# lm3410-boost-flashlight-driver-20mm-mk-1.net
KiCad netlist of a schematic drawn in EAGLE
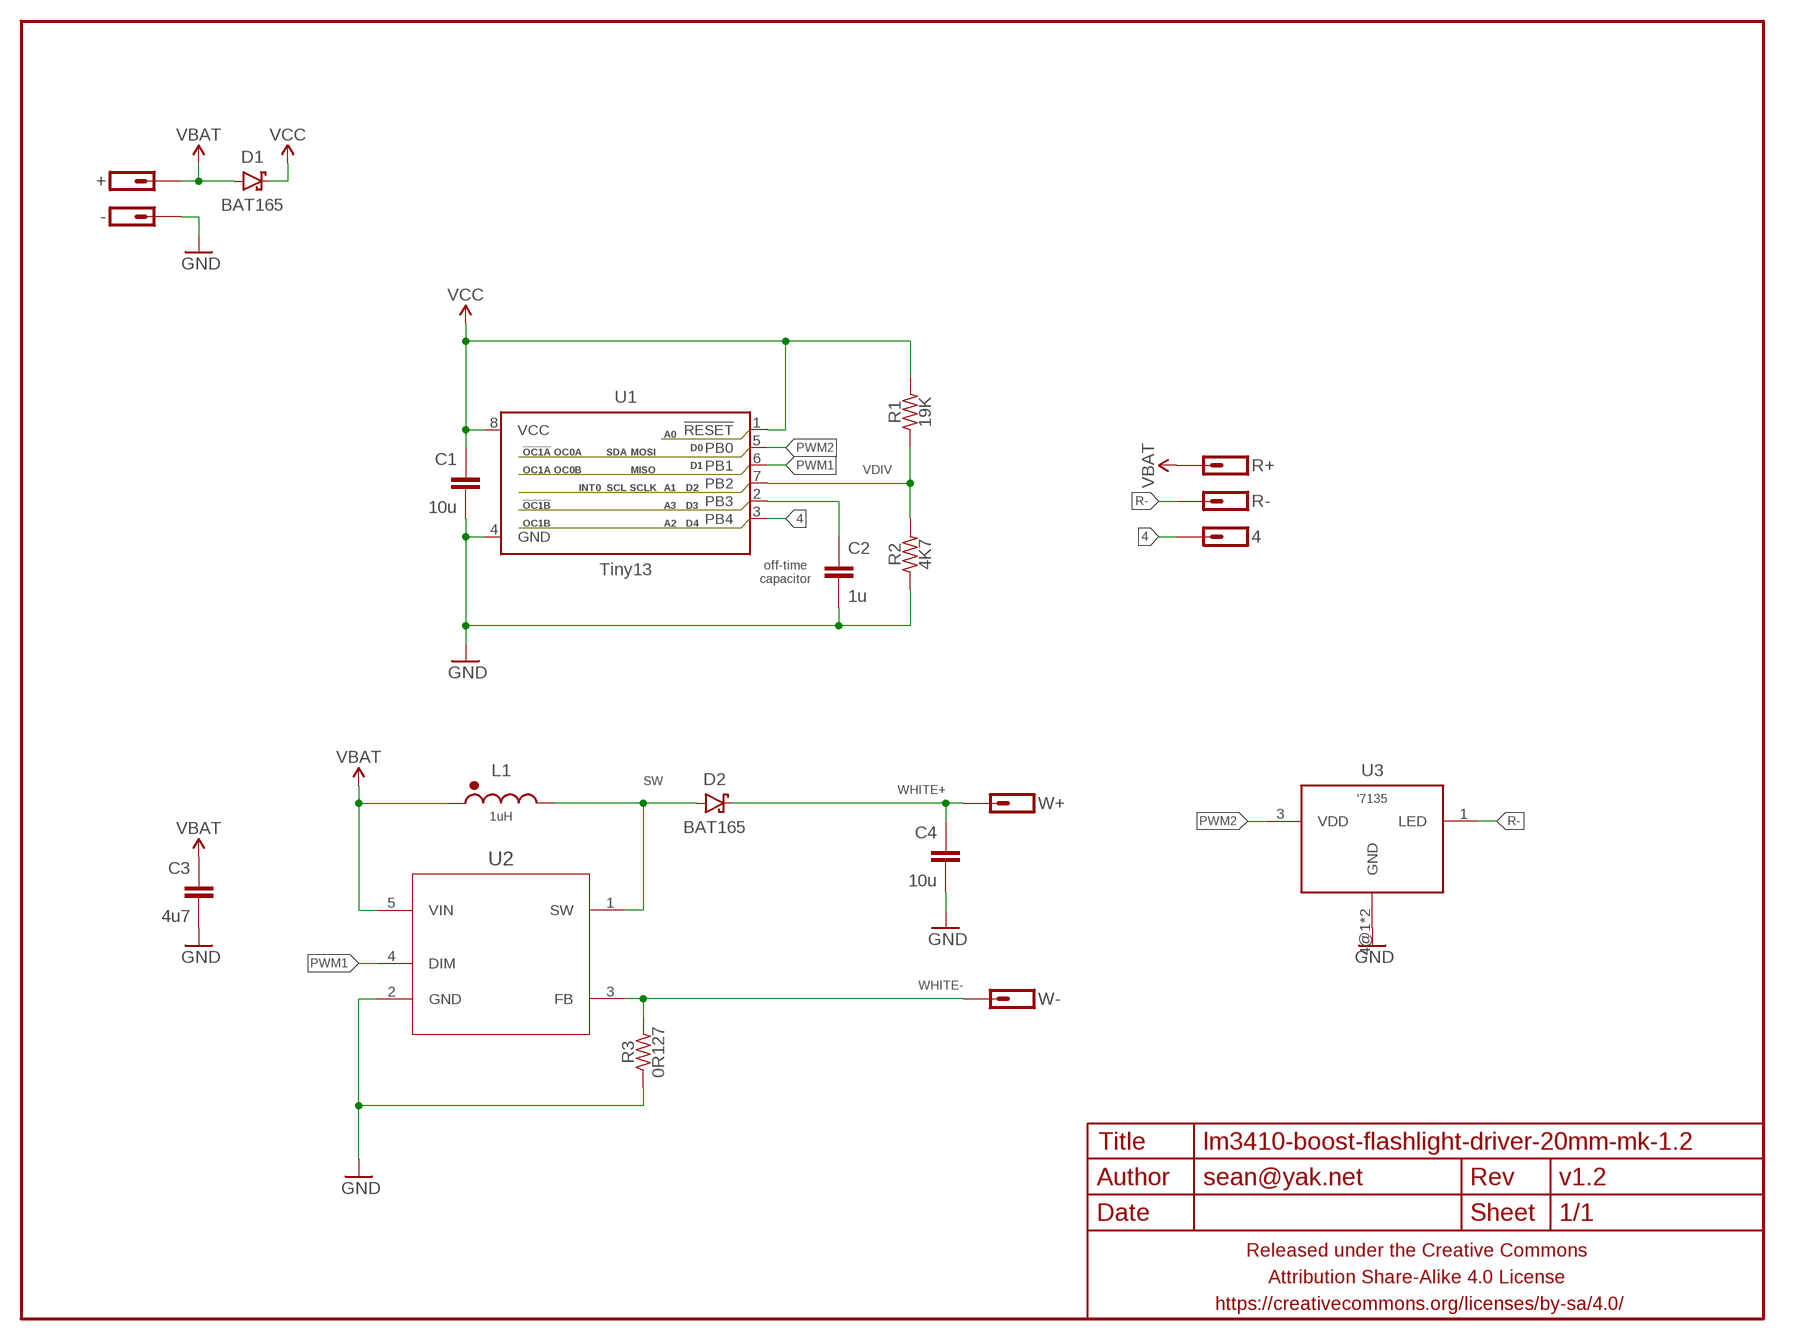
[diagram p0: schematic, sheet 1]

(export (version "E")
  (design (tool "Eeschema 10.0.6"))
  (components
    (comp (ref "+")
      (value "M01PTH-1MM-CIR-NS")
      (footprint "eagle-import:1X01-1MM-CIR-NS")
      (libsource (lib "eagle-import") (part "M01PTH-1MM-CIR-NS"))
    )
    (comp (ref "-")
      (value "M01NOT-A-VIA-NOPE")
      (footprint "eagle-import:1X01_NOSILK_NOSTOP")
      (libsource (lib "eagle-import") (part "M01NOT-A-VIA-NOPE"))
    )
    (comp (ref "4")
      (value "M01SMD-1MM-DIA-NS")
      (footprint "eagle-import:1X01-SMD-1MM-DIA-NS")
      (libsource (lib "eagle-import") (part "M01SMD-1MM-DIA-NS"))
    )
    (comp (ref "C1")
      (value "10u")
      (footprint "eagle-import:C0603-TIGHTER")
      (libsource (lib "eagle-import") (part "CAPACITOR-CERAMICC0603-TIGHTER"))
    )
    (comp (ref "C2")
      (value "1u")
      (footprint "eagle-import:C0603-TIGHTER")
      (libsource (lib "eagle-import") (part "CAPACITOR-CERAMICC0603-TIGHTER"))
    )
    (comp (ref "C3")
      (value "4u7")
      (footprint "eagle-import:C0603-TIGHTER")
      (libsource (lib "eagle-import") (part "CAPACITOR-CERAMICC0603-TIGHTER"))
    )
    (comp (ref "C4")
      (value "10u")
      (footprint "eagle-import:C0603-TIGHTER")
      (libsource (lib "eagle-import") (part "CAPACITOR-CERAMICC0603-TIGHTER"))
    )
    (comp (ref "D1")
      (value "BAT165")
      (footprint "eagle-import:SOD323-SCHOTTKY")
      (libsource (lib "eagle-import") (part "DIODE-SCHOTTKYSOD323"))
    )
    (comp (ref "D2")
      (value "BAT165")
      (footprint "eagle-import:SOD323-SCHOTTKY")
      (libsource (lib "eagle-import") (part "DIODE-SCHOTTKYSOD323"))
    )
    (comp (ref "FRAME1")
      (value "FRAME-LETTERNO_PACKAGE")
      (footprint "eagle-import:DUMMY")
      (fields (field (name "DESIGNER") "sean@yak.net") (field (name "VERSION") "v1.2"))
      (libsource (lib "eagle-import") (part "FRAME-LETTERNO_PACKAGE"))
    )
    (comp (ref "L1")
      (value "1uH")
      (footprint "eagle-import:PFL2512")
      (libsource (lib "eagle-import") (part "INDUCTORPFL2512"))
    )
    (comp (ref "R+")
      (value "M01SMD-1MM-DIA-NS")
      (footprint "eagle-import:1X01-SMD-1MM-DIA-NS")
      (libsource (lib "eagle-import") (part "M01SMD-1MM-DIA-NS"))
    )
    (comp (ref "R-")
      (value "M01SMD-1MM-DIA-NS")
      (footprint "eagle-import:1X01-SMD-1MM-DIA-NS")
      (libsource (lib "eagle-import") (part "M01SMD-1MM-DIA-NS"))
    )
    (comp (ref "R1")
      (value "19K")
      (footprint "eagle-import:R0603-TIGHTER")
      (libsource (lib "eagle-import") (part "RESISTORR0603-TIGHTER"))
    )
    (comp (ref "R2")
      (value "4K7")
      (footprint "eagle-import:R0603-TIGHTER")
      (libsource (lib "eagle-import") (part "RESISTORR0603-TIGHTER"))
    )
    (comp (ref "R3")
      (value "0R127")
      (footprint "eagle-import:R0805")
      (libsource (lib "eagle-import") (part "RESISTORR0805"))
    )
    (comp (ref "U1")
      (value "Tiny13")
      (footprint "eagle-import:SO08-NARROWER")
      (libsource (lib "eagle-import") (part "ATTINY13SOIC-NARROWPADS"))
    )
    (comp (ref "U2")
      (value "LM3410XMF")
      (footprint "eagle-import:SOT95P285X120-5N")
      (libsource (lib "eagle-import") (part "LM3410XMF"))
    )
    (comp (ref "U3")
      (value "'7135")
      (footprint "eagle-import:SOT89-NOTHERM")
      (libsource (lib "eagle-import") (part "AMC7135SOT-89-NOTHERM"))
    )
    (comp (ref "W+")
      (value "M01PTH-1.2MM-NS")
      (footprint "eagle-import:1X01-1.2MM-NS")
      (libsource (lib "eagle-import") (part "M01PTH-1.2MM-NS"))
    )
    (comp (ref "W-")
      (value "M01PTH-1.2MM-NS")
      (footprint "eagle-import:1X01-1.2MM-NS")
      (libsource (lib "eagle-import") (part "M01PTH-1.2MM-NS"))
    )
  )
  (nets
    (net (code "1") (name "/SW") (class "Default")
      (node (ref "D2") (pin "A") (pinfunction "A_A") (pintype "passive"))
      (node (ref "L1") (pin "P$2") (pinfunction "2_P$2") (pintype "passive"))
      (node (ref "U2") (pin "1") (pinfunction "SW_1") (pintype "output"))
    )
    (net (code "2") (name "/VDIV") (class "Default")
      (node (ref "R1") (pin "1") (pinfunction "1_1") (pintype "passive"))
      (node (ref "R2") (pin "2") (pinfunction "2_2") (pintype "passive"))
      (node (ref "U1") (pin "7") (pinfunction "PB2_7") (pintype "bidirectional"))
    )
    (net (code "3") (name "/WHITE+") (class "Default")
      (node (ref "C4") (pin "1") (pinfunction "1_1") (pintype "passive"))
      (node (ref "D2") (pin "C") (pinfunction "C_C") (pintype "passive"))
      (node (ref "W+") (pin "P$1") (pinfunction "1_P$1") (pintype "passive"))
    )
    (net (code "4") (name "/WHITE-") (class "Default")
      (node (ref "R3") (pin "2") (pinfunction "2_2") (pintype "passive"))
      (node (ref "U2") (pin "3") (pinfunction "FB_3") (pintype "input"))
      (node (ref "W-") (pin "P$1") (pinfunction "1_P$1") (pintype "passive"))
    )
    (net (code "5") (name "4") (class "Default")
      (node (ref "4") (pin "P$1") (pinfunction "1_P$1") (pintype "passive"))
      (node (ref "U1") (pin "3") (pinfunction "PB4_3") (pintype "bidirectional"))
    )
    (net (code "6") (name "GND") (class "Default")
      (node (ref "-") (pin "P$1") (pinfunction "1_P$1") (pintype "passive"))
      (node (ref "C1") (pin "2") (pinfunction "2_2") (pintype "passive"))
      (node (ref "C2") (pin "2") (pinfunction "2_2") (pintype "passive"))
      (node (ref "C3") (pin "2") (pinfunction "2_2") (pintype "passive"))
      (node (ref "C4") (pin "2") (pinfunction "2_2") (pintype "passive"))
      (node (ref "R2") (pin "1") (pinfunction "1_1") (pintype "passive"))
      (node (ref "R3") (pin "1") (pinfunction "1_1") (pintype "passive"))
      (node (ref "U1") (pin "4") (pinfunction "GND_4") (pintype "bidirectional"))
      (node (ref "U2") (pin "2") (pinfunction "GND_2") (pintype "passive"))
      (node (ref "U3") (pin "4@1") (pinfunction "GND_4@1") (pintype "bidirectional"))
      (node (ref "U3") (pin "4@2") (pinfunction "GND_4@2") (pintype "bidirectional"))
    )
    (net (code "7") (name "Net-(U1-PB3)") (class "Default")
      (node (ref "C2") (pin "1") (pinfunction "1_1") (pintype "passive"))
      (node (ref "U1") (pin "2") (pinfunction "PB3_2") (pintype "bidirectional"))
    )
    (net (code "8") (name "PWM1") (class "Default")
      (node (ref "U1") (pin "6") (pinfunction "PB1_6") (pintype "bidirectional"))
      (node (ref "U2") (pin "4") (pinfunction "DIM_4") (pintype "input"))
    )
    (net (code "9") (name "PWM2") (class "Default")
      (node (ref "U1") (pin "5") (pinfunction "PB0_5") (pintype "bidirectional"))
      (node (ref "U3") (pin "3") (pinfunction "VDD_3") (pintype "bidirectional"))
    )
    (net (code "10") (name "R-") (class "Default")
      (node (ref "R-") (pin "P$1") (pinfunction "1_P$1") (pintype "passive"))
      (node (ref "U3") (pin "1") (pinfunction "LED_1") (pintype "bidirectional"))
    )
    (net (code "11") (name "VBAT") (class "Default")
      (node (ref "+") (pin "1") (pinfunction "1_1") (pintype "passive"))
      (node (ref "C3") (pin "1") (pinfunction "1_1") (pintype "passive"))
      (node (ref "D1") (pin "A") (pinfunction "A_A") (pintype "passive"))
      (node (ref "L1") (pin "P$1") (pinfunction "1_P$1") (pintype "passive"))
      (node (ref "R+") (pin "P$1") (pinfunction "1_P$1") (pintype "passive"))
      (node (ref "U2") (pin "5") (pinfunction "VIN_5") (pintype "power_in"))
    )
    (net (code "12") (name "VCC") (class "Default")
      (node (ref "C1") (pin "1") (pinfunction "1_1") (pintype "passive"))
      (node (ref "D1") (pin "C") (pinfunction "C_C") (pintype "passive"))
      (node (ref "R1") (pin "2") (pinfunction "2_2") (pintype "passive"))
      (node (ref "U1") (pin "1") (pinfunction "~{RESET}_1") (pintype "bidirectional"))
      (node (ref "U1") (pin "8") (pinfunction "VCC_8") (pintype "bidirectional"))
    )
  )
)
